# SparkFun_LSM303C_6_DOF_IMU_Breakout.net
KiCad netlist of a schematic drawn in EAGLE
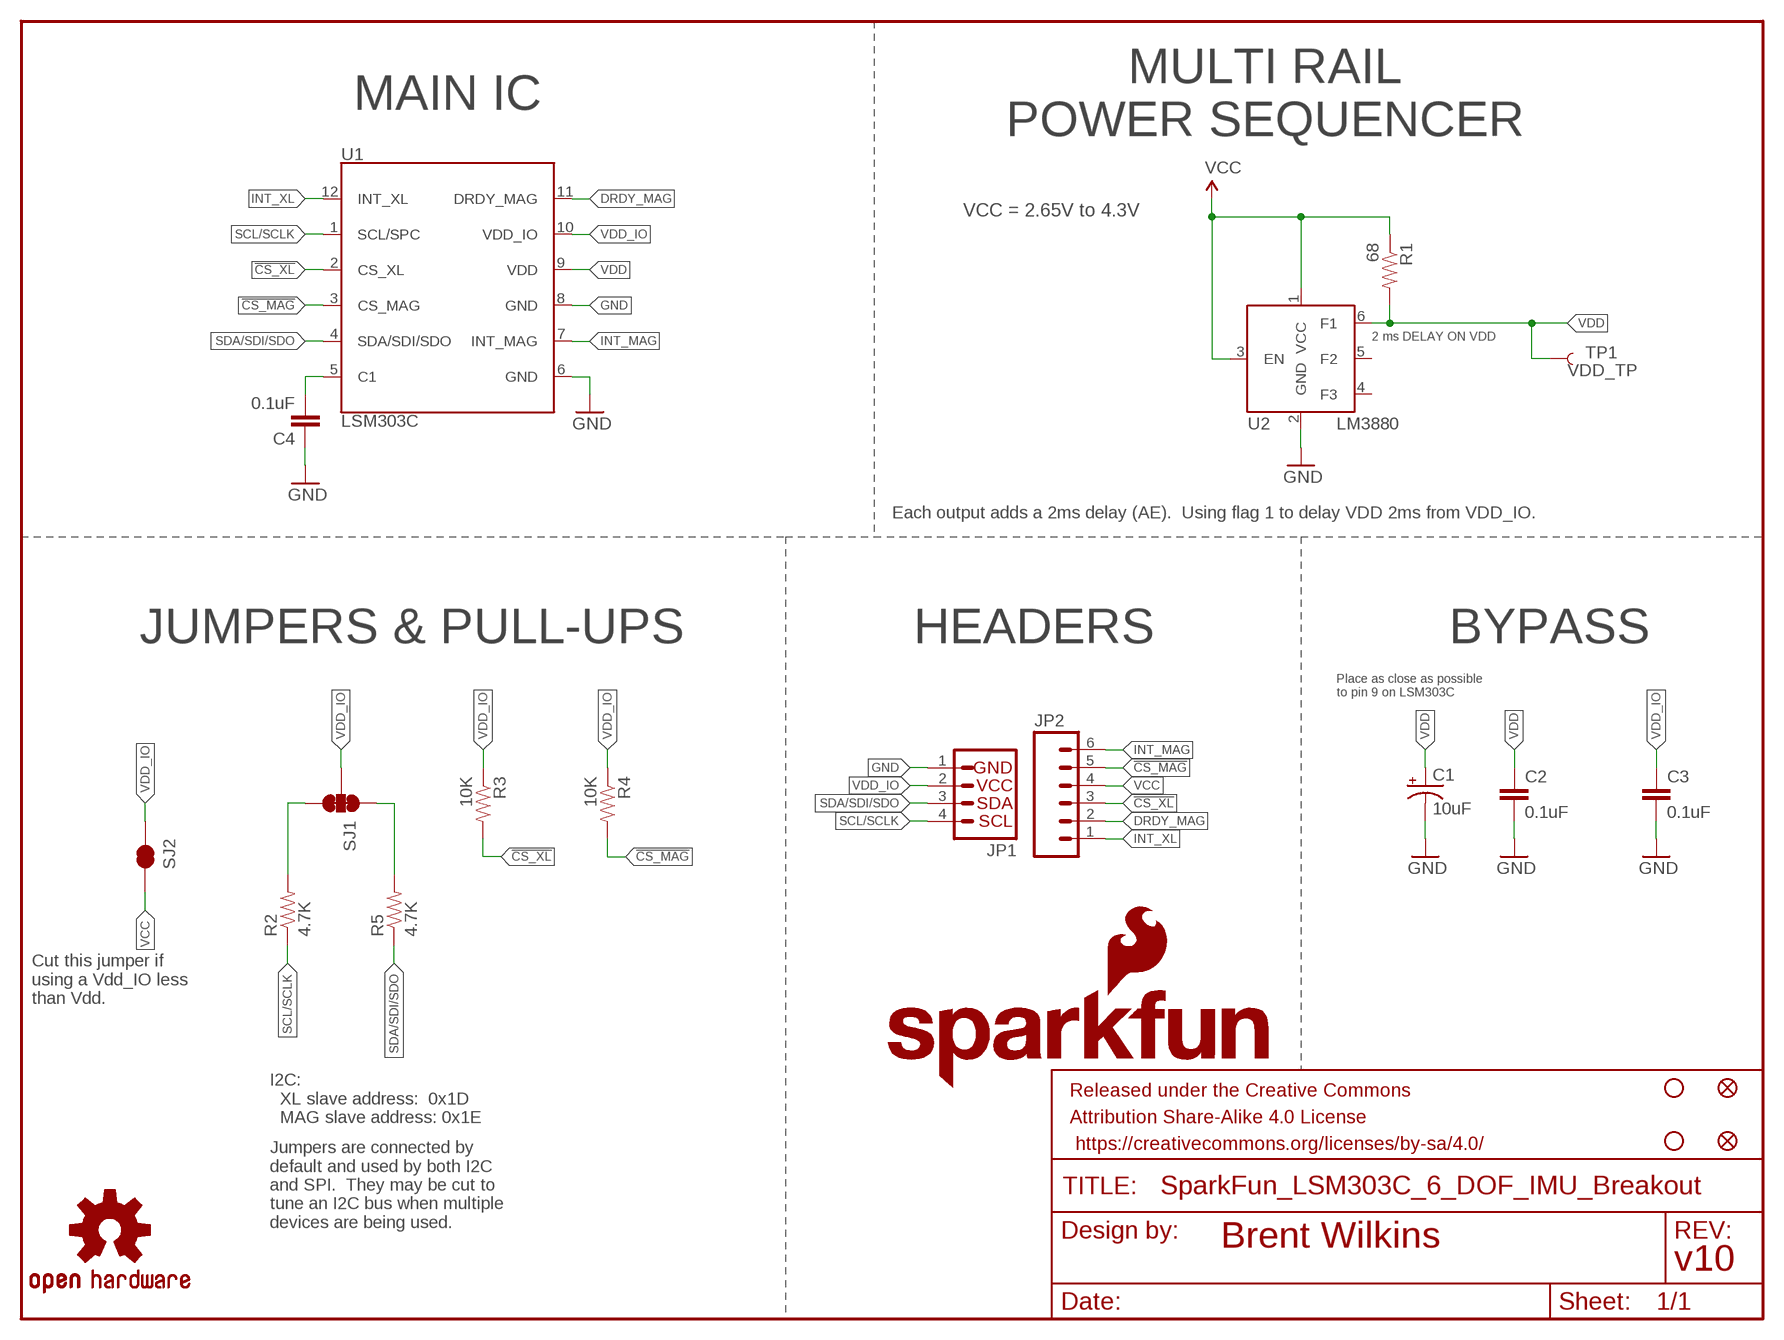
[diagram p0: schematic, sheet 1]

(export (version "E")
  (design (tool "Eeschema 10.0.6"))
  (components
    (comp (ref "C1")
      (value "10uF")
      (footprint "eagle-import:EIA3216")
      (libsource (lib "eagle-import") (part "CAP_POL1206"))
    )
    (comp (ref "C2")
      (value "0.1uF")
      (footprint "eagle-import:0603-CAP")
      (libsource (lib "eagle-import") (part "0.1UF-25V(+80/-20%)(0603)"))
    )
    (comp (ref "C3")
      (value "0.1uF")
      (footprint "eagle-import:0603-CAP")
      (libsource (lib "eagle-import") (part "0.1UF-25V(+80/-20%)(0603)"))
    )
    (comp (ref "C4")
      (value "0.1uF")
      (footprint "eagle-import:0603-CAP")
      (libsource (lib "eagle-import") (part "0.1UF-25V(+80/-20%)(0603)"))
    )
    (comp (ref "FID1")
      (value "FIDUCIAL1X2")
      (footprint "eagle-import:FIDUCIAL-1X2")
      (libsource (lib "eagle-import") (part "FIDUCIAL1X2"))
    )
    (comp (ref "FID2")
      (value "FIDUCIAL1X2")
      (footprint "eagle-import:FIDUCIAL-1X2")
      (libsource (lib "eagle-import") (part "FIDUCIAL1X2"))
    )
    (comp (ref "FRAME1")
      (value "FRAME-LETTER")
      (footprint "eagle-import:CREATIVE_COMMONS")
      (libsource (lib "eagle-import") (part "FRAME-LETTER"))
    )
    (comp (ref "JP1")
      (value "I2C_STANDARD")
      (footprint "eagle-import:1X04")
      (libsource (lib "eagle-import") (part "I2C_STANDARD"))
    )
    (comp (ref "JP2")
      (value "M06SILK_FEMALE_PTH")
      (footprint "eagle-import:1X06")
      (libsource (lib "eagle-import") (part "M06SILK_FEMALE_PTH"))
    )
    (comp (ref "LOGO1")
      (value "SFE_LOGO_NAME.1_INCH")
      (footprint "eagle-import:SFE_LOGO_NAME_.1")
      (libsource (lib "eagle-import") (part "SFE_LOGO_NAME.1_INCH"))
    )
    (comp (ref "LOGO2")
      (value "SFE_LOGO_FLAME.1EXP")
      (footprint "eagle-import:SFE_LOGO_FLAME_COPPER_EXPOSED_.1")
      (libsource (lib "eagle-import") (part "SFE_LOGO_FLAME.1EXP"))
    )
    (comp (ref "R1")
      (value "68")
      (footprint "eagle-import:0603-RES")
      (libsource (lib "eagle-import") (part "RESISTOR0603-RES"))
    )
    (comp (ref "R2")
      (value "4.7K")
      (footprint "eagle-import:0603-RES")
      (fields (field (name "PROD_ID") "RES-07857"))
      (libsource (lib "eagle-import") (part "4.7KOHM-1/10W-1%(0603)"))
    )
    (comp (ref "R3")
      (value "10K")
      (footprint "eagle-import:0603-RES")
      (libsource (lib "eagle-import") (part "10KOHM-1/10W-1%(0603)0603"))
    )
    (comp (ref "R4")
      (value "10K")
      (footprint "eagle-import:0603-RES")
      (libsource (lib "eagle-import") (part "10KOHM-1/10W-1%(0603)0603"))
    )
    (comp (ref "R5")
      (value "4.7K")
      (footprint "eagle-import:0603-RES")
      (fields (field (name "PROD_ID") "RES-07857"))
      (libsource (lib "eagle-import") (part "4.7KOHM-1/10W-1%(0603)"))
    )
    (comp (ref "SJ1")
      (value "JUMPER-PAD-3-NC_BY_TRACE")
      (footprint "eagle-import:PAD-JUMPER-3-3OF3_NC_BY_TRACE_YES_SILK_FULL_BOX")
      (libsource (lib "eagle-import") (part "JUMPER-PAD-3-NC_BY_TRACE"))
    )
    (comp (ref "SJ2")
      (value "JUMPER-PAD-2-NC_BY_TRACE")
      (footprint "eagle-import:PAD-JUMPER-2-NC_BY_TRACE_YES_SILK")
      (libsource (lib "eagle-import") (part "JUMPER-PAD-2-NC_BY_TRACE"))
    )
    (comp (ref "STANDOFF1")
      (value "STAND-OFF")
      (footprint "eagle-import:STAND-OFF")
      (libsource (lib "eagle-import") (part "STAND-OFF"))
    )
    (comp (ref "STANDOFF2")
      (value "STAND-OFF")
      (footprint "eagle-import:STAND-OFF")
      (libsource (lib "eagle-import") (part "STAND-OFF"))
    )
    (comp (ref "TP1")
      (value "VDD_TP")
      (footprint "eagle-import:TP_15TH")
      (libsource (lib "eagle-import") (part "TEST-POINTTP_15TH_THRU"))
    )
    (comp (ref "U$8")
      (value "OSHW-LOGOS")
      (footprint "eagle-import:OSHW-LOGO-S")
      (libsource (lib "eagle-import") (part "OSHW-LOGOS"))
    )
    (comp (ref "U1")
      (value "LSM303C")
      (footprint "eagle-import:LGA-12")
      (libsource (lib "eagle-import") (part "LSM303C"))
    )
    (comp (ref "U2")
      (value "LM3880")
      (footprint "eagle-import:SOT23-6")
      (fields (field (name "PROD_ID") "IC-12558"))
      (libsource (lib "eagle-import") (part "LM3880/-QI"))
    )
  )
  (nets
    (net (code "1") (name "/~{CS_MAG}") (class "Default")
      (node (ref "JP2") (pin "5") (pinfunction "5_5") (pintype "passive"))
      (node (ref "R4") (pin "2") (pinfunction "2_2") (pintype "passive"))
      (node (ref "U1") (pin "3") (pinfunction "CS_MAG_3") (pintype "bidirectional"))
    )
    (net (code "2") (name "/~{CS_XL}") (class "Default")
      (node (ref "JP2") (pin "3") (pinfunction "3_3") (pintype "passive"))
      (node (ref "R3") (pin "2") (pinfunction "2_2") (pintype "passive"))
      (node (ref "U1") (pin "2") (pinfunction "CS_XL_2") (pintype "bidirectional"))
    )
    (net (code "3") (name "DRDY_MAG") (class "Default")
      (node (ref "JP2") (pin "2") (pinfunction "2_2") (pintype "passive"))
      (node (ref "U1") (pin "11") (pinfunction "DRDY_MAG_11") (pintype "bidirectional"))
    )
    (net (code "4") (name "GND") (class "Default")
      (node (ref "C1") (pin "C") (pinfunction "-_C") (pintype "passive"))
      (node (ref "C2") (pin "2") (pinfunction "2_2") (pintype "passive"))
      (node (ref "C3") (pin "2") (pinfunction "2_2") (pintype "passive"))
      (node (ref "C4") (pin "1") (pinfunction "1_1") (pintype "passive"))
      (node (ref "JP1") (pin "1") (pinfunction "1_1") (pintype "passive"))
      (node (ref "U1") (pin "6") (pinfunction "GND_6") (pintype "bidirectional"))
      (node (ref "U1") (pin "8") (pinfunction "GND_8") (pintype "bidirectional"))
      (node (ref "U2") (pin "2") (pinfunction "GND_2") (pintype "bidirectional"))
    )
    (net (code "5") (name "INT_MAG") (class "Default")
      (node (ref "JP2") (pin "6") (pinfunction "6_6") (pintype "passive"))
      (node (ref "U1") (pin "7") (pinfunction "INT_MAG_7") (pintype "bidirectional"))
    )
    (net (code "6") (name "INT_XL") (class "Default")
      (node (ref "JP2") (pin "1") (pinfunction "1_1") (pintype "passive"))
      (node (ref "U1") (pin "12") (pinfunction "INT_XL_12") (pintype "bidirectional"))
    )
    (net (code "7") (name "Net-(R2-Pad2)") (class "Default")
      (node (ref "R2") (pin "2") (pinfunction "2_2") (pintype "passive"))
      (node (ref "SJ1") (pin "3") (pinfunction "3_3") (pintype "passive"))
    )
    (net (code "8") (name "Net-(R5-Pad2)") (class "Default")
      (node (ref "R5") (pin "2") (pinfunction "2_2") (pintype "passive"))
      (node (ref "SJ1") (pin "1") (pinfunction "1_1") (pintype "passive"))
    )
    (net (code "9") (name "Net-(U1-C1)") (class "Default")
      (node (ref "C4") (pin "2") (pinfunction "2_2") (pintype "passive"))
      (node (ref "U1") (pin "5") (pinfunction "C1_5") (pintype "bidirectional"))
    )
    (net (code "10") (name "SCL{slash}SCLK") (class "Default")
      (node (ref "JP1") (pin "4") (pinfunction "4_4") (pintype "passive"))
      (node (ref "R2") (pin "1") (pinfunction "1_1") (pintype "passive"))
      (node (ref "U1") (pin "1") (pinfunction "SCL/SPC_1") (pintype "bidirectional"))
    )
    (net (code "11") (name "SDA{slash}SDI{slash}SDO") (class "Default")
      (node (ref "JP1") (pin "3") (pinfunction "3_3") (pintype "passive"))
      (node (ref "R5") (pin "1") (pinfunction "1_1") (pintype "passive"))
      (node (ref "U1") (pin "4") (pinfunction "SDA/SDI/SDO_4") (pintype "bidirectional"))
    )
    (net (code "12") (name "VCC") (class "Default")
      (node (ref "JP2") (pin "4") (pinfunction "4_4") (pintype "passive"))
      (node (ref "R1") (pin "1") (pinfunction "1_1") (pintype "passive"))
      (node (ref "SJ2") (pin "2") (pinfunction "2_2") (pintype "passive"))
      (node (ref "U2") (pin "1") (pinfunction "VCC_1") (pintype "bidirectional"))
      (node (ref "U2") (pin "3") (pinfunction "EN_3") (pintype "bidirectional"))
    )
    (net (code "13") (name "VDD") (class "Default")
      (node (ref "C1") (pin "A") (pinfunction "+_A") (pintype "passive"))
      (node (ref "C2") (pin "1") (pinfunction "1_1") (pintype "passive"))
      (node (ref "R1") (pin "2") (pinfunction "2_2") (pintype "passive"))
      (node (ref "TP1") (pin "P$1") (pinfunction "1_P$1") (pintype "bidirectional"))
      (node (ref "U1") (pin "9") (pinfunction "VDD_9") (pintype "bidirectional"))
      (node (ref "U2") (pin "6") (pinfunction "F1_6") (pintype "bidirectional"))
    )
    (net (code "14") (name "VDD_IO") (class "Default")
      (node (ref "C3") (pin "1") (pinfunction "1_1") (pintype "passive"))
      (node (ref "JP1") (pin "2") (pinfunction "2_2") (pintype "passive"))
      (node (ref "R3") (pin "1") (pinfunction "1_1") (pintype "passive"))
      (node (ref "R4") (pin "1") (pinfunction "1_1") (pintype "passive"))
      (node (ref "SJ1") (pin "2") (pinfunction "2_2") (pintype "passive"))
      (node (ref "SJ2") (pin "1") (pinfunction "1_1") (pintype "passive"))
      (node (ref "U1") (pin "10") (pinfunction "VDD_IO_10") (pintype "bidirectional"))
    )
    (net (code "15") (name "unconnected-(U2-F2-Pad5)") (class "Default")
      (node (ref "U2") (pin "5") (pinfunction "F2_5") (pintype "bidirectional"))
    )
    (net (code "16") (name "unconnected-(U2-F3-Pad4)") (class "Default")
      (node (ref "U2") (pin "4") (pinfunction "F3_4") (pintype "bidirectional"))
    )
  )
)
